# MINIOLED.net
KiCad netlist of a schematic drawn in Altium Designer
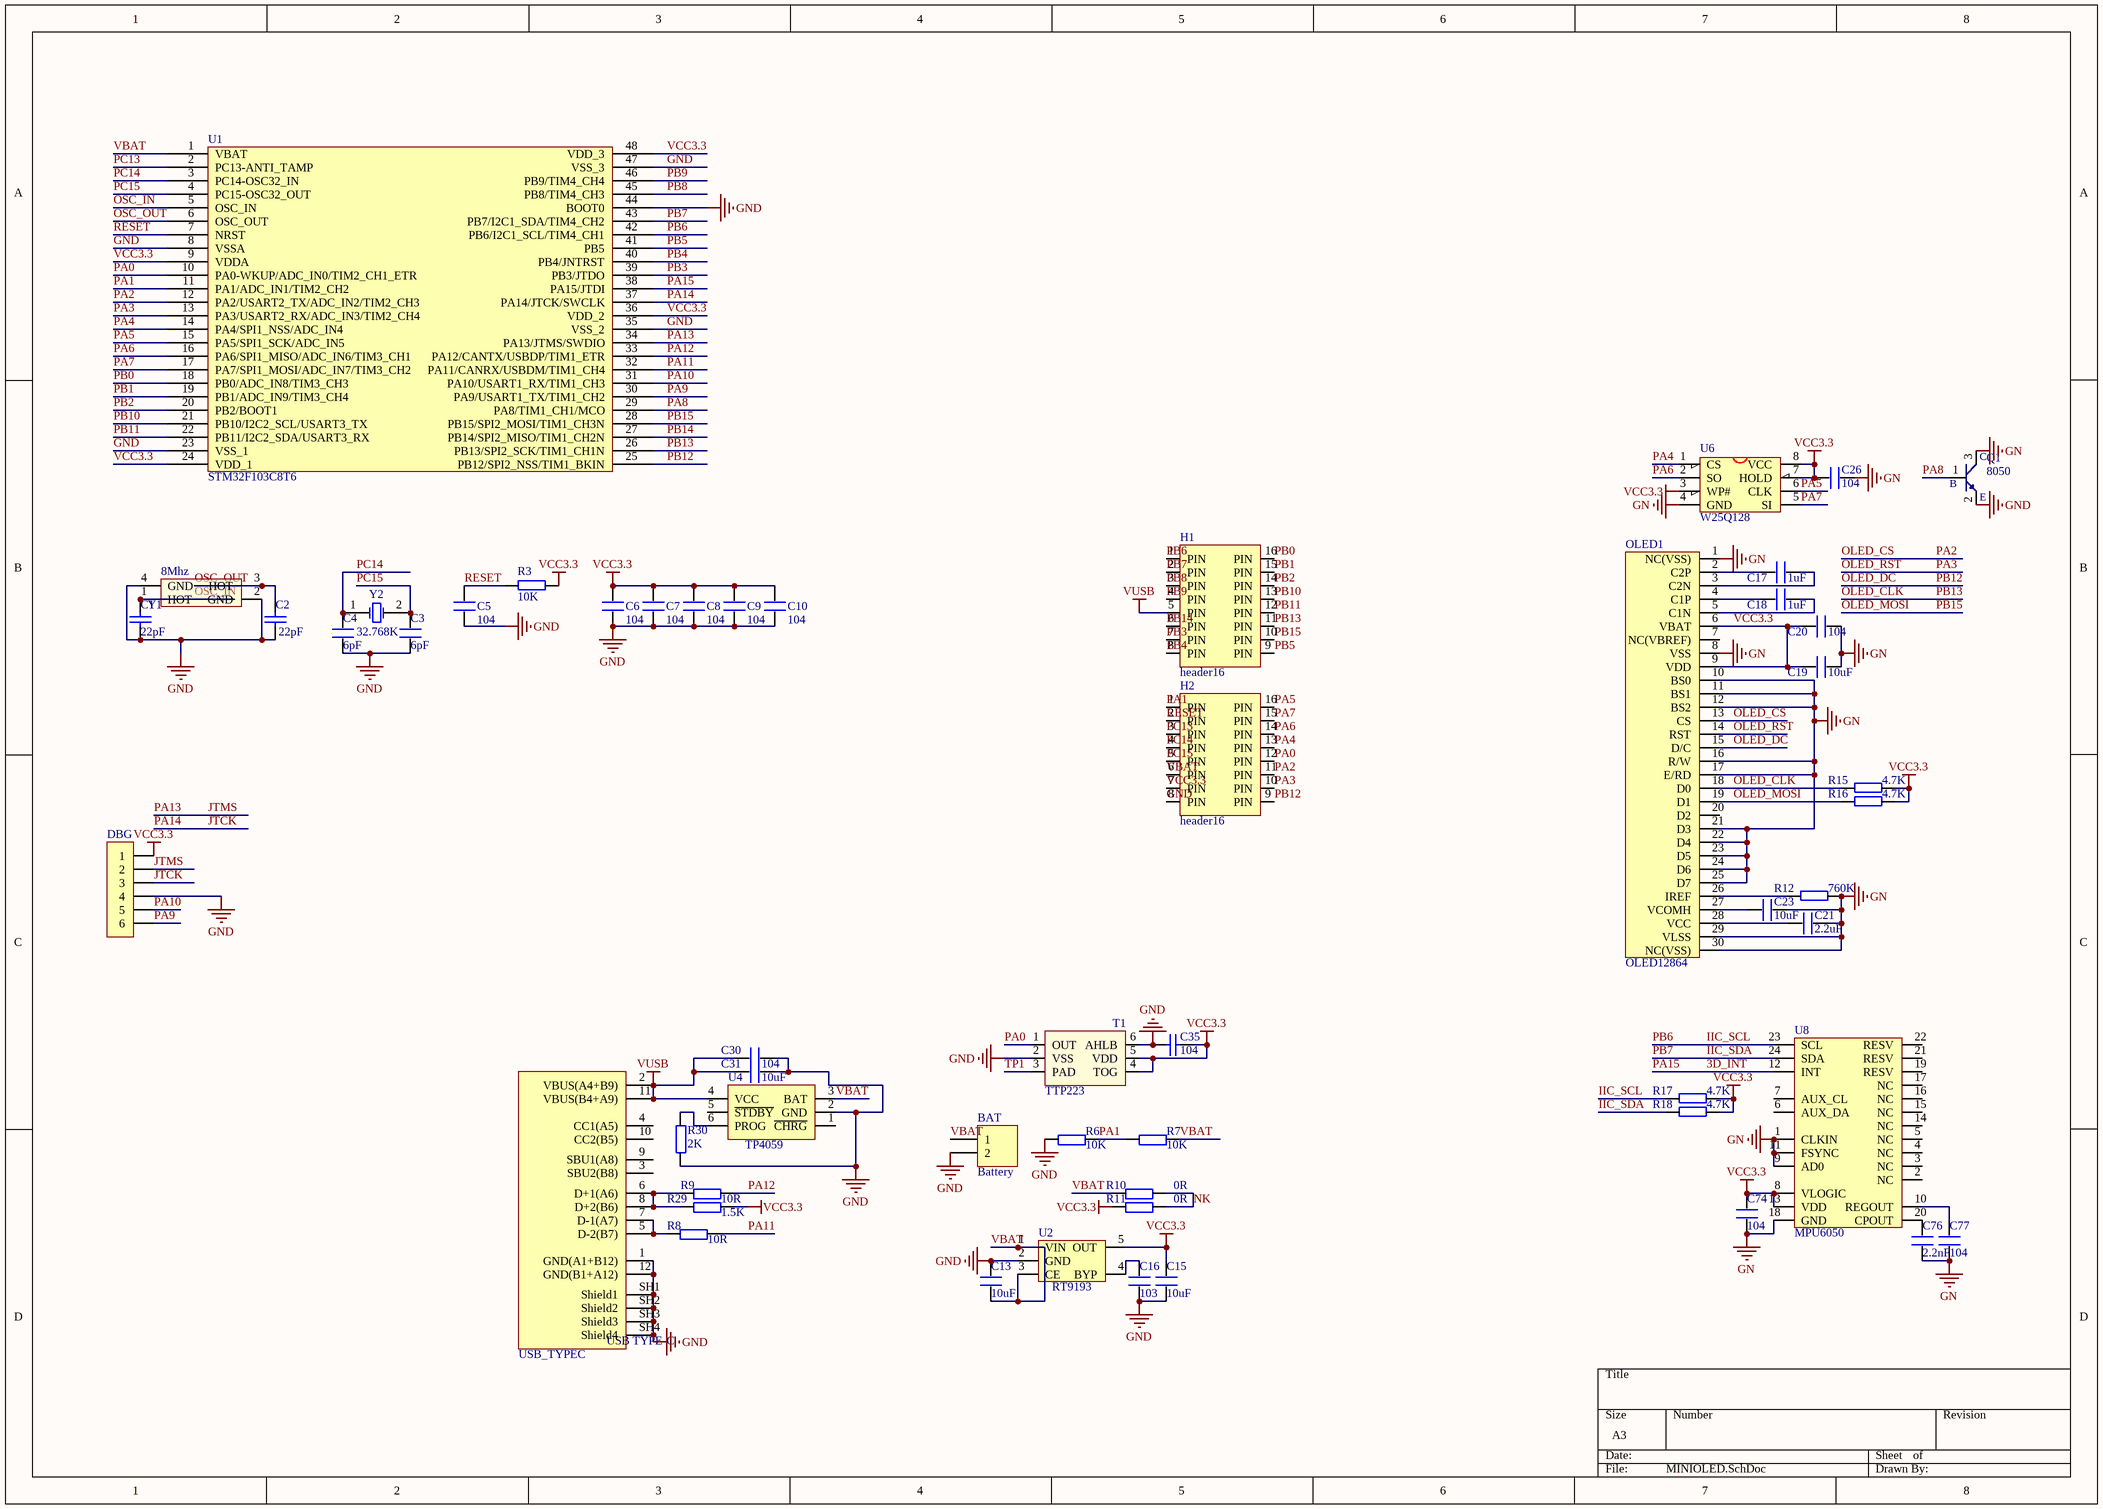
[diagram p0: MINIOLED.SchDoc]

(export (version "E")
  (design (tool "Eeschema 10.0.6"))
  (components
    (comp (ref "BAT")
      (value "Battery")
      (footprint "HDR2.54-LI-2P")
      (description "Header, 2-Pin")
      (fields (field (name "PUBLISHER") "Altium Limited"))
      (libsource (lib "MiniFly ") (part "Header 2"))
    )
    (comp (ref "C1") (value "22pF") (footprint "C 0603_L") (libsource (lib "L476") (part "CAP")))
    (comp (ref "C2") (value "22pF") (footprint "C 0603_L") (libsource (lib "L476") (part "CAP")))
    (comp (ref "C3")
      (value "6pF")
      (footprint "C 0603_L")
      (libsource (lib "WarShip V3 STM32103封装库") (part "C"))
    )
    (comp (ref "C4")
      (value "6pF")
      (footprint "C 0603_L")
      (libsource (lib "WarShip V3 STM32103封装库") (part "C"))
    )
    (comp (ref "C5")
      (value "104")
      (footprint "C 0603_L")
      (libsource (lib "WarShip V3 STM32103封装库") (part "C"))
    )
    (comp (ref "C6")
      (value "104")
      (footprint "C 0603_L")
      (libsource (lib "WarShip V3 STM32103封装库") (part "C"))
    )
    (comp (ref "C7")
      (value "104")
      (footprint "C 0603_L")
      (libsource (lib "WarShip V3 STM32103封装库") (part "C"))
    )
    (comp (ref "C8")
      (value "104")
      (footprint "C 0603_L")
      (libsource (lib "WarShip V3 STM32103封装库") (part "C"))
    )
    (comp (ref "C9")
      (value "104")
      (footprint "C 0603_L")
      (libsource (lib "WarShip V3 STM32103封装库") (part "C"))
    )
    (comp (ref "C10")
      (value "104")
      (footprint "C 0603_L")
      (libsource (lib "WarShip V3 STM32103封装库") (part "C"))
    )
    (comp (ref "C13")
      (value "10uF")
      (footprint "C 0603_L")
      (libsource (lib "WarShip V3 STM32103封装库") (part "C"))
    )
    (comp (ref "C15")
      (value "10uF")
      (footprint "C 0603_L")
      (libsource (lib "WarShip V3 STM32103封装库") (part "C"))
    )
    (comp (ref "C16")
      (value "103")
      (footprint "C 0603_L")
      (libsource (lib "WarShip V3 STM32103封装库") (part "C"))
    )
    (comp (ref "C17")
      (value "1uF")
      (footprint "C 0603_L")
      (libsource (lib "WarShip V3 STM32103封装库") (part "C"))
    )
    (comp (ref "C18")
      (value "1uF")
      (footprint "C 0603_L")
      (libsource (lib "WarShip V3 STM32103封装库") (part "C"))
    )
    (comp (ref "C19")
      (value "10uF")
      (footprint "C 0603_L")
      (libsource (lib "WarShip V3 STM32103封装库") (part "C"))
    )
    (comp (ref "C20")
      (value "104")
      (footprint "C 0603_L")
      (libsource (lib "WarShip V3 STM32103封装库") (part "C"))
    )
    (comp (ref "C21")
      (value "2.2uF")
      (footprint "C 0603_L")
      (libsource (lib "WarShip V3 STM32103封装库") (part "C"))
    )
    (comp (ref "C23")
      (value "10uF")
      (footprint "C 0603_L")
      (libsource (lib "WarShip V3 STM32103封装库") (part "C"))
    )
    (comp (ref "C26")
      (value "104")
      (footprint "C 0603_L")
      (libsource (lib "WarShip V3 STM32103封装库") (part "C"))
    )
    (comp (ref "C30")
      (value "104")
      (footprint "C 0603_L")
      (libsource (lib "WarShip V3 STM32103封装库") (part "C"))
    )
    (comp (ref "C31")
      (value "10uF")
      (footprint "C 0603_L")
      (libsource (lib "WarShip V3 STM32103封装库") (part "C"))
    )
    (comp (ref "C35")
      (value "104")
      (footprint "C 0603_L")
      (libsource (lib "Pandora_STM32L4_Board_V2.4") (part "C-0603-SMD"))
    )
    (comp (ref "C74") (value "104") (footprint "C 0603_L") (libsource (lib "MYCOMLIB") (part "C")))
    (comp (ref "C76") (value "2.2nF") (footprint "C 0603_L") (libsource (lib "MYCOMLIB") (part "C")))
    (comp (ref "C77") (value "104") (footprint "C 0603_L") (libsource (lib "MYCOMLIB") (part "C")))
    (comp (ref "DBG")
      (value "GPS&COMPASS")
      (footprint "SH1.0_6P")
      (description "6P接插件")
      (fields (field (name "版权归属") "源创客"))
      (libsource (lib "ATKF405 V1.1") (part "Header 6"))
    )
    (comp (ref "H1")
      (value "header16")
      (footprint "F_16PIN")
      (description "表贴母座16P")
      (libsource (lib "LovelessingSch") (part "Header2X8"))
    )
    (comp (ref "H2")
      (value "header16")
      (footprint "F_16PIN")
      (description "表贴母座16P")
      (libsource (lib "LovelessingSch") (part "Header2X8"))
    )
    (comp (ref "OLED1")
      (value "OLED12864")
      (footprint "OLED1.3")
      (libsource (lib "OLED模块封装库") (part "OLED12864"))
    )
    (comp (ref "Q1")
      (value "8050")
      (footprint "SOT23-3L")
      (libsource (lib "LovelessingSch") (part "8050NPN"))
    )
    (comp (ref "R3")
      (value "10K")
      (footprint "R 0603_L")
      (libsource (lib "WarShip V3 STM32103封装库") (part "R"))
    )
    (comp (ref "R6")
      (value "10K")
      (footprint "R 0603_L")
      (libsource (lib "WarShip V3 STM32103封装库") (part "R"))
    )
    (comp (ref "R7")
      (value "10K")
      (footprint "R 0603_L")
      (libsource (lib "WarShip V3 STM32103封装库") (part "R"))
    )
    (comp (ref "R8")
      (value "10R")
      (footprint "R 0603_L")
      (libsource (lib "WarShip V3 STM32103封装库") (part "R"))
    )
    (comp (ref "R9")
      (value "10R")
      (footprint "R 0603_L")
      (libsource (lib "WarShip V3 STM32103封装库") (part "R"))
    )
    (comp (ref "R10")
      (value "0R")
      (footprint "R 0603_L")
      (libsource (lib "WarShip V3 STM32103封装库") (part "R"))
    )
    (comp (ref "R11")
      (value "0R")
      (footprint "R 0603_L")
      (libsource (lib "WarShip V3 STM32103封装库") (part "R"))
    )
    (comp (ref "R12")
      (value "760K")
      (footprint "R 0603_L")
      (libsource (lib "WarShip V3 STM32103封装库") (part "R"))
    )
    (comp (ref "R15")
      (value "4.7K")
      (footprint "R 0603_L")
      (libsource (lib "WarShip V3 STM32103封装库") (part "R"))
    )
    (comp (ref "R16")
      (value "4.7K")
      (footprint "R 0603_L")
      (libsource (lib "WarShip V3 STM32103封装库") (part "R"))
    )
    (comp (ref "R17")
      (value "4.7K")
      (footprint "R 0603_L")
      (libsource (lib "WarShip V3 STM32103封装库") (part "R"))
    )
    (comp (ref "R18")
      (value "4.7K")
      (footprint "R 0603_L")
      (libsource (lib "WarShip V3 STM32103封装库") (part "R"))
    )
    (comp (ref "R29")
      (value "1.5K")
      (footprint "R 0603_L")
      (libsource (lib "WarShip V3 STM32103封装库") (part "R"))
    )
    (comp (ref "R30")
      (value "2K")
      (footprint "R 0603_L")
      (libsource (lib "WarShip V3 STM32103封装库") (part "R"))
    )
    (comp (ref "T1")
      (value "TTP223")
      (footprint "SOT23-6L")
      (libsource (lib "nrf52832model") (part "TTP223"))
    )
    (comp (ref "U1")
      (value "STM32F103C8T6")
      (footprint "LQFP48 7X7_L")
      (libsource (lib "Pandora_STM32L4_Board_V2.4") (part "U-STM32F103C8T6"))
    )
    (comp (ref "U2")
      (value "RT9193")
      (footprint "SOT23-5L")
      (description "3.3V 500mA LDO")
      (libsource (lib "STM32H743核心板封装库") (part "CAT6219-330TD"))
    )
    (comp (ref "U4")
      (value "TP4059")
      (footprint "SOT23-6L")
      (libsource (lib "ATK-2014-09-12") (part "TP4059"))
    )
    (comp (ref "U6")
      (value "W25Q128")
      (footprint "SOP8W_L")
      (description "W25X16;SST25VF016;MX25L1605")
      (libsource (lib "WarShip V3 STM32103封装库") (part "W25X16"))
    )
    (comp (ref "U8")
      (value "MPU6050")
      (footprint "QFN24 4x4_N")
      (description "9轴运动处理传感器")
      (libsource (lib "ALIENTEK_COMPONENT") (part "MPU6050"))
    )
    (comp (ref "USB_TYPEC")
      (value "USB TypeC")
      (footprint "USB Type-C")
      (description "12P TypeC 母座")
      (libsource (lib "ESP32_Weather") (part "USB Type-C"))
    )
    (comp (ref "Y1")
      (value "8Mhz")
      (footprint "OSC32254Pmini")
      (description "3225贴片无源晶振")
      (libsource (lib "ALIENTEK_COMPONENT") (part "XTAL_3225"))
    )
    (comp (ref "Y2")
      (value "32.768K")
      (footprint "OSC 3215-2P")
      (description "Crystal Oscillator")
      (fields (field (name "PUBLISHER") "Altium Limited"))
      (libsource (lib "WarShip V3 STM32103封装库") (part "XTAL"))
    )
  )
  (nets
    (net (code "1") (name "/3D_INT") (class "Default")
      (node (ref "U1") (pin "38") (pinfunction "PA15/JTDI_38") (pintype "passive"))
      (node (ref "U8") (pin "12") (pinfunction "INT_12") (pintype "passive"))
    )
    (net (code "2") (name "/IIC_SCL") (class "Default")
      (node (ref "H1") (pin "1") (pinfunction "PIN_1") (pintype "passive"))
      (node (ref "R17") (pin "2") (pintype "passive"))
      (node (ref "U1") (pin "42") (pinfunction "PB6/I2C1_SCL/TIM4_CH1_42") (pintype "passive"))
      (node (ref "U8") (pin "23") (pinfunction "SCL_23") (pintype "passive"))
    )
    (net (code "3") (name "/IIC_SDA") (class "Default")
      (node (ref "H1") (pin "2") (pinfunction "PIN_2") (pintype "passive"))
      (node (ref "R18") (pin "2") (pintype "passive"))
      (node (ref "U1") (pin "43") (pinfunction "PB7/I2C1_SDA/TIM4_CH2_43") (pintype "passive"))
      (node (ref "U8") (pin "24") (pinfunction "SDA_24") (pintype "passive"))
    )
    (net (code "4") (name "/JTCK") (class "Default")
      (node (ref "DBG") (pin "3") (pinfunction "3_3") (pintype "passive"))
      (node (ref "U1") (pin "37") (pinfunction "PA14/JTCK/SWCLK_37") (pintype "passive"))
    )
    (net (code "5") (name "/JTMS") (class "Default")
      (node (ref "DBG") (pin "2") (pinfunction "2_2") (pintype "passive"))
      (node (ref "U1") (pin "34") (pinfunction "PA13/JTMS/SWDIO_34") (pintype "passive"))
    )
    (net (code "6") (name "/NK") (class "Default")
      (node (ref "R10") (pin "2") (pintype "passive"))
      (node (ref "R11") (pin "2") (pintype "passive"))
    )
    (net (code "7") (name "/OLED_CLK") (class "Default")
      (node (ref "H1") (pin "11") (pinfunction "PIN_11") (pintype "passive"))
      (node (ref "OLED1") (pin "18") (pinfunction "D0_18") (pintype "passive"))
      (node (ref "R15") (pin "2") (pintype "passive"))
      (node (ref "U1") (pin "26") (pinfunction "PB13/SPI2_SCK/TIM1_CH1N_26") (pintype "passive"))
    )
    (net (code "8") (name "/OLED_CS") (class "Default")
      (node (ref "H2") (pin "11") (pinfunction "PIN_11") (pintype "passive"))
      (node (ref "OLED1") (pin "13") (pinfunction "CS_13") (pintype "passive"))
      (node (ref "U1") (pin "12") (pinfunction "PA2/USART2_TX/ADC_IN2/TIM2_CH3_12") (pintype "passive"))
    )
    (net (code "9") (name "/OLED_DC") (class "Default")
      (node (ref "H2") (pin "9") (pinfunction "PIN_9") (pintype "passive"))
      (node (ref "OLED1") (pin "15") (pinfunction "D/C_15") (pintype "passive"))
      (node (ref "U1") (pin "25") (pinfunction "PB12/SPI2_NSS/TIM1_BKIN_25") (pintype "passive"))
    )
    (net (code "10") (name "/OLED_MOSI") (class "Default")
      (node (ref "H1") (pin "10") (pinfunction "PIN_10") (pintype "passive"))
      (node (ref "OLED1") (pin "19") (pinfunction "D1_19") (pintype "passive"))
      (node (ref "R16") (pin "2") (pintype "passive"))
      (node (ref "U1") (pin "28") (pinfunction "PB15/SPI2_MOSI/TIM1_CH3N_28") (pintype "passive"))
    )
    (net (code "11") (name "/OLED_RST") (class "Default")
      (node (ref "H2") (pin "10") (pinfunction "PIN_10") (pintype "passive"))
      (node (ref "OLED1") (pin "14") (pinfunction "RST_14") (pintype "passive"))
      (node (ref "U1") (pin "13") (pinfunction "PA3/USART2_RX/ADC_IN3/TIM2_CH4_13") (pintype "passive"))
    )
    (net (code "12") (name "/OSC_IN") (class "Default")
      (node (ref "C1") (pin "2") (pinfunction "2_2") (pintype "passive"))
      (node (ref "U1") (pin "5") (pinfunction "OSC_IN_5") (pintype "passive"))
      (node (ref "Y1") (pin "1") (pinfunction "HOT_1") (pintype "passive"))
    )
    (net (code "13") (name "/OSC_OUT") (class "Default")
      (node (ref "C2") (pin "2") (pinfunction "2_2") (pintype "passive"))
      (node (ref "U1") (pin "6") (pinfunction "OSC_OUT_6") (pintype "passive"))
      (node (ref "Y1") (pin "3") (pinfunction "HOT_3") (pintype "passive"))
    )
    (net (code "14") (name "/PA0") (class "Default")
      (node (ref "H2") (pin "12") (pinfunction "PIN_12") (pintype "passive"))
      (node (ref "T1") (pin "1") (pinfunction "OUT_1") (pintype "passive"))
      (node (ref "U1") (pin "10") (pinfunction "PA0-WKUP/ADC_IN0/TIM2_CH1_ETR_10") (pintype "passive"))
    )
    (net (code "15") (name "/PA1") (class "Default")
      (node (ref "H2") (pin "1") (pinfunction "PIN_1") (pintype "passive"))
      (node (ref "R6") (pin "2") (pintype "passive"))
      (node (ref "R7") (pin "1") (pintype "passive"))
      (node (ref "U1") (pin "11") (pinfunction "PA1/ADC_IN1/TIM2_CH2_11") (pintype "passive"))
    )
    (net (code "16") (name "/PA4") (class "Default")
      (node (ref "H2") (pin "13") (pinfunction "PIN_13") (pintype "passive"))
      (node (ref "U1") (pin "14") (pinfunction "PA4/SPI1_NSS/ADC_IN4_14") (pintype "passive"))
      (node (ref "U6") (pin "1") (pinfunction "CS_1") (pintype "passive"))
    )
    (net (code "17") (name "/PA5") (class "Default")
      (node (ref "H2") (pin "16") (pinfunction "PIN_16") (pintype "passive"))
      (node (ref "U1") (pin "15") (pinfunction "PA5/SPI1_SCK/ADC_IN5_15") (pintype "passive"))
      (node (ref "U6") (pin "6") (pinfunction "CLK_6") (pintype "passive"))
    )
    (net (code "18") (name "/PA6") (class "Default")
      (node (ref "H2") (pin "14") (pinfunction "PIN_14") (pintype "passive"))
      (node (ref "U1") (pin "16") (pinfunction "PA6/SPI1_MISO/ADC_IN6/TIM3_CH1_16") (pintype "passive"))
      (node (ref "U6") (pin "2") (pinfunction "SO_2") (pintype "passive"))
    )
    (net (code "19") (name "/PA7") (class "Default")
      (node (ref "H2") (pin "15") (pinfunction "PIN_15") (pintype "passive"))
      (node (ref "U1") (pin "17") (pinfunction "PA7/SPI1_MOSI/ADC_IN7/TIM3_CH2_17") (pintype "passive"))
      (node (ref "U6") (pin "5") (pinfunction "SI_5") (pintype "passive"))
    )
    (net (code "20") (name "/PA8") (class "Default")
      (node (ref "Q1") (pin "1") (pinfunction "B_1") (pintype "passive"))
      (node (ref "U1") (pin "29") (pinfunction "PA8/TIM1_CH1/MCO_29") (pintype "passive"))
    )
    (net (code "21") (name "/PA9") (class "Default")
      (node (ref "DBG") (pin "6") (pinfunction "6_6") (pintype "passive"))
      (node (ref "U1") (pin "30") (pinfunction "PA9/USART1_TX/TIM1_CH2_30") (pintype "passive"))
    )
    (net (code "22") (name "/PA10") (class "Default")
      (node (ref "DBG") (pin "5") (pinfunction "5_5") (pintype "passive"))
      (node (ref "U1") (pin "31") (pinfunction "PA10/USART1_RX/TIM1_CH3_31") (pintype "passive"))
    )
    (net (code "23") (name "/PA11") (class "Default")
      (node (ref "R8") (pin "2") (pintype "passive"))
      (node (ref "U1") (pin "32") (pinfunction "PA11/CANRX/USBDM/TIM1_CH4_32") (pintype "passive"))
    )
    (net (code "24") (name "/PA12") (class "Default")
      (node (ref "R9") (pin "2") (pintype "passive"))
      (node (ref "U1") (pin "33") (pinfunction "PA12/CANTX/USBDP/TIM1_ETR_33") (pintype "passive"))
    )
    (net (code "25") (name "/PB0") (class "Default")
      (node (ref "H1") (pin "16") (pinfunction "PIN_16") (pintype "passive"))
      (node (ref "U1") (pin "18") (pinfunction "PB0/ADC_IN8/TIM3_CH3_18") (pintype "passive"))
    )
    (net (code "26") (name "/PB1") (class "Default")
      (node (ref "H1") (pin "15") (pinfunction "PIN_15") (pintype "passive"))
      (node (ref "U1") (pin "19") (pinfunction "PB1/ADC_IN9/TIM3_CH4_19") (pintype "passive"))
    )
    (net (code "27") (name "/PB2") (class "Default")
      (node (ref "H1") (pin "14") (pinfunction "PIN_14") (pintype "passive"))
      (node (ref "U1") (pin "20") (pinfunction "PB2/BOOT1_20") (pintype "passive"))
    )
    (net (code "28") (name "/PB3") (class "Default")
      (node (ref "H1") (pin "7") (pinfunction "PIN_7") (pintype "passive"))
      (node (ref "U1") (pin "39") (pinfunction "PB3/JTDO_39") (pintype "passive"))
    )
    (net (code "29") (name "/PB4") (class "Default")
      (node (ref "H1") (pin "8") (pinfunction "PIN_8") (pintype "passive"))
      (node (ref "U1") (pin "40") (pinfunction "PB4/JNTRST_40") (pintype "passive"))
    )
    (net (code "30") (name "/PB5") (class "Default")
      (node (ref "H1") (pin "9") (pinfunction "PIN_9") (pintype "passive"))
      (node (ref "U1") (pin "41") (pinfunction "PB5_41") (pintype "passive"))
    )
    (net (code "31") (name "/PB8") (class "Default")
      (node (ref "H1") (pin "3") (pinfunction "PIN_3") (pintype "passive"))
      (node (ref "U1") (pin "45") (pinfunction "PB8/TIM4_CH3_45") (pintype "passive"))
    )
    (net (code "32") (name "/PB9") (class "Default")
      (node (ref "H1") (pin "4") (pinfunction "PIN_4") (pintype "passive"))
      (node (ref "U1") (pin "46") (pinfunction "PB9/TIM4_CH4_46") (pintype "passive"))
    )
    (net (code "33") (name "/PB10") (class "Default")
      (node (ref "H1") (pin "13") (pinfunction "PIN_13") (pintype "passive"))
      (node (ref "U1") (pin "21") (pinfunction "PB10/I2C2_SCL/USART3_TX_21") (pintype "passive"))
    )
    (net (code "34") (name "/PB11") (class "Default")
      (node (ref "H1") (pin "12") (pinfunction "PIN_12") (pintype "passive"))
      (node (ref "U1") (pin "22") (pinfunction "PB11/I2C2_SDA/USART3_RX_22") (pintype "passive"))
    )
    (net (code "35") (name "/PB14") (class "Default")
      (node (ref "H1") (pin "6") (pinfunction "PIN_6") (pintype "passive"))
      (node (ref "U1") (pin "27") (pinfunction "PB14/SPI2_MISO/TIM1_CH2N_27") (pintype "passive"))
    )
    (net (code "36") (name "/PC13") (class "Default")
      (node (ref "H2") (pin "3") (pinfunction "PIN_3") (pintype "passive"))
      (node (ref "U1") (pin "2") (pinfunction "PC13-ANTI_TAMP_2") (pintype "passive"))
    )
    (net (code "37") (name "/PC14") (class "Default")
      (node (ref "C4") (pin "2") (pintype "passive"))
      (node (ref "H2") (pin "4") (pinfunction "PIN_4") (pintype "passive"))
      (node (ref "U1") (pin "3") (pinfunction "PC14-OSC32_IN_3") (pintype "passive"))
      (node (ref "Y2") (pin "1") (pinfunction "OSC1_1") (pintype "passive"))
    )
    (net (code "38") (name "/PC15") (class "Default")
      (node (ref "C3") (pin "2") (pintype "passive"))
      (node (ref "H2") (pin "5") (pinfunction "PIN_5") (pintype "passive"))
      (node (ref "U1") (pin "4") (pinfunction "PC15-OSC32_OUT_4") (pintype "passive"))
      (node (ref "Y2") (pin "2") (pinfunction "OSC2_2") (pintype "passive"))
    )
    (net (code "39") (name "/RESET") (class "Default")
      (node (ref "C5") (pin "2") (pintype "passive"))
      (node (ref "H2") (pin "2") (pinfunction "PIN_2") (pintype "passive"))
      (node (ref "R3") (pin "2") (pintype "passive"))
      (node (ref "U1") (pin "7") (pinfunction "NRST_7") (pintype "passive"))
    )
    (net (code "40") (name "/TP1") (class "Default")
      (node (ref "T1") (pin "3") (pinfunction "PAD_3") (pintype "passive"))
    )
    (net (code "41") (name "/VBAT") (class "Default")
      (node (ref "BAT") (pin "1") (pinfunction "1_1") (pintype "passive"))
      (node (ref "C13") (pin "1") (pintype "passive"))
      (node (ref "H2") (pin "6") (pinfunction "PIN_6") (pintype "passive"))
      (node (ref "R10") (pin "1") (pintype "passive"))
      (node (ref "R7") (pin "2") (pintype "passive"))
      (node (ref "U1") (pin "1") (pinfunction "VBAT_1") (pintype "passive"))
      (node (ref "U2") (pin "1") (pinfunction "VIN_1") (pintype "passive"))
      (node (ref "U2") (pin "3") (pinfunction "CE_3") (pintype "passive"))
      (node (ref "U4") (pin "3") (pinfunction "BAT_3") (pintype "passive"))
    )
    (net (code "42") (name "GN") (class "Default")
      (node (ref "C19") (pin "1") (pintype "passive"))
      (node (ref "C20") (pin "1") (pintype "passive"))
      (node (ref "C21") (pin "1") (pintype "passive"))
      (node (ref "C23") (pin "1") (pintype "passive"))
      (node (ref "C26") (pin "2") (pintype "passive"))
      (node (ref "C74") (pin "1") (pintype "passive"))
      (node (ref "C76") (pin "1") (pintype "passive"))
      (node (ref "C77") (pin "2") (pintype "passive"))
      (node (ref "OLED1") (pin "1") (pinfunction "NC(VSS)_1") (pintype "passive"))
      (node (ref "OLED1") (pin "10") (pinfunction "BS0_10") (pintype "passive"))
      (node (ref "OLED1") (pin "11") (pinfunction "BS1_11") (pintype "passive"))
      (node (ref "OLED1") (pin "12") (pinfunction "BS2_12") (pintype "passive"))
      (node (ref "OLED1") (pin "16") (pinfunction "R/W_16") (pintype "passive"))
      (node (ref "OLED1") (pin "17") (pinfunction "E/RD_17") (pintype "passive"))
      (node (ref "OLED1") (pin "21") (pinfunction "D3_21") (pintype "passive"))
      (node (ref "OLED1") (pin "22") (pinfunction "D4_22") (pintype "passive"))
      (node (ref "OLED1") (pin "23") (pinfunction "D5_23") (pintype "passive"))
      (node (ref "OLED1") (pin "24") (pinfunction "D6_24") (pintype "passive"))
      (node (ref "OLED1") (pin "25") (pinfunction "D7_25") (pintype "passive"))
      (node (ref "OLED1") (pin "29") (pinfunction "VLSS_29") (pintype "passive"))
      (node (ref "OLED1") (pin "30") (pinfunction "NC(VSS)_30") (pintype "passive"))
      (node (ref "OLED1") (pin "8") (pinfunction "VSS_8") (pintype "passive"))
      (node (ref "Q1") (pin "3") (pinfunction "C_3") (pintype "passive"))
      (node (ref "R12") (pin "1") (pintype "passive"))
      (node (ref "U6") (pin "4") (pinfunction "GND_4") (pintype "passive"))
      (node (ref "U8") (pin "1") (pinfunction "CLKIN_1") (pintype "passive"))
      (node (ref "U8") (pin "11") (pinfunction "FSYNC_11") (pintype "passive"))
      (node (ref "U8") (pin "18") (pinfunction "GND_18") (pintype "passive"))
      (node (ref "U8") (pin "9") (pinfunction "AD0_9") (pintype "passive"))
    )
    (net (code "43") (name "GND") (class "Default")
      (node (ref "BAT") (pin "2") (pinfunction "2_2") (pintype "passive"))
      (node (ref "C1") (pin "1") (pinfunction "1_1") (pintype "passive"))
      (node (ref "C10") (pin "1") (pintype "passive"))
      (node (ref "C13") (pin "2") (pintype "passive"))
      (node (ref "C15") (pin "1") (pintype "passive"))
      (node (ref "C16") (pin "1") (pintype "passive"))
      (node (ref "C2") (pin "1") (pinfunction "1_1") (pintype "passive"))
      (node (ref "C3") (pin "1") (pintype "passive"))
      (node (ref "C30") (pin "1") (pintype "passive"))
      (node (ref "C31") (pin "1") (pintype "passive"))
      (node (ref "C35") (pin "2") (pinfunction "2_2") (pintype "passive"))
      (node (ref "C4") (pin "1") (pintype "passive"))
      (node (ref "C5") (pin "1") (pintype "passive"))
      (node (ref "C6") (pin "1") (pintype "passive"))
      (node (ref "C7") (pin "1") (pintype "passive"))
      (node (ref "C8") (pin "1") (pintype "passive"))
      (node (ref "C9") (pin "1") (pintype "passive"))
      (node (ref "DBG") (pin "4") (pinfunction "4_4") (pintype "passive"))
      (node (ref "H2") (pin "8") (pinfunction "PIN_8") (pintype "passive"))
      (node (ref "Q1") (pin "2") (pinfunction "E_2") (pintype "passive"))
      (node (ref "R30") (pin "1") (pintype "passive"))
      (node (ref "R6") (pin "1") (pintype "passive"))
      (node (ref "T1") (pin "2") (pinfunction "VSS_2") (pintype "passive"))
      (node (ref "T1") (pin "6") (pinfunction "AHLB_6") (pintype "passive"))
      (node (ref "U1") (pin "23") (pinfunction "VSS_1_23") (pintype "passive"))
      (node (ref "U1") (pin "35") (pinfunction "VSS_2_35") (pintype "passive"))
      (node (ref "U1") (pin "44") (pinfunction "BOOT0_44") (pintype "passive"))
      (node (ref "U1") (pin "47") (pinfunction "VSS_3_47") (pintype "passive"))
      (node (ref "U1") (pin "8") (pinfunction "VSSA_8") (pintype "passive"))
      (node (ref "U2") (pin "2") (pinfunction "GND_2") (pintype "passive"))
      (node (ref "U4") (pin "2") (pinfunction "GND_2") (pintype "passive"))
      (node (ref "USB_TYPEC") (pin "1") (pinfunction "GND(A1+B12)_1") (pintype "passive"))
      (node (ref "USB_TYPEC") (pin "12") (pinfunction "GND(B1+A12)_12") (pintype "passive"))
      (node (ref "USB_TYPEC") (pin "SH1") (pinfunction "Shield1_SH1") (pintype "passive"))
      (node (ref "USB_TYPEC") (pin "SH2") (pinfunction "Shield2_SH2") (pintype "passive"))
      (node (ref "USB_TYPEC") (pin "SH3") (pinfunction "Shield3_SH3") (pintype "passive"))
      (node (ref "USB_TYPEC") (pin "SH4") (pinfunction "Shield4_SH4") (pintype "passive"))
      (node (ref "Y1") (pin "2") (pinfunction "GND_2") (pintype "passive"))
      (node (ref "Y1") (pin "4") (pinfunction "GND_4") (pintype "passive"))
    )
    (net (code "44") (name "Net-(OLED1-C1N)") (class "Default")
      (node (ref "C18") (pin "1") (pintype "passive"))
      (node (ref "OLED1") (pin "5") (pinfunction "C1N_5") (pintype "passive"))
    )
    (net (code "45") (name "Net-(OLED1-C1P)") (class "Default")
      (node (ref "C18") (pin "2") (pintype "passive"))
      (node (ref "OLED1") (pin "4") (pinfunction "C1P_4") (pintype "passive"))
    )
    (net (code "46") (name "Net-(OLED1-C2N)") (class "Default")
      (node (ref "C17") (pin "1") (pintype "passive"))
      (node (ref "OLED1") (pin "3") (pinfunction "C2N_3") (pintype "passive"))
    )
    (net (code "47") (name "Net-(OLED1-C2P)") (class "Default")
      (node (ref "C17") (pin "2") (pintype "passive"))
      (node (ref "OLED1") (pin "2") (pinfunction "C2P_2") (pintype "passive"))
    )
    (net (code "48") (name "Net-(OLED1-IREF)") (class "Default")
      (node (ref "OLED1") (pin "26") (pinfunction "IREF_26") (pintype "passive"))
      (node (ref "R12") (pin "2") (pintype "passive"))
    )
    (net (code "49") (name "Net-(OLED1-VCC)") (class "Default")
      (node (ref "C21") (pin "2") (pintype "passive"))
      (node (ref "OLED1") (pin "28") (pinfunction "VCC_28") (pintype "passive"))
    )
    (net (code "50") (name "Net-(OLED1-VCOMH)") (class "Default")
      (node (ref "C23") (pin "2") (pintype "passive"))
      (node (ref "OLED1") (pin "27") (pinfunction "VCOMH_27") (pintype "passive"))
    )
    (net (code "51") (name "Net-(U2-BYP)") (class "Default")
      (node (ref "C16") (pin "2") (pintype "passive"))
      (node (ref "U2") (pin "4") (pinfunction "BYP_4") (pintype "passive"))
    )
    (net (code "52") (name "Net-(U4-PROG)") (class "Default")
      (node (ref "R30") (pin "2") (pintype "passive"))
      (node (ref "U4") (pin "6") (pinfunction "PROG_6") (pintype "passive"))
    )
    (net (code "53") (name "Net-(U8-CPOUT)") (class "Default")
      (node (ref "C76") (pin "2") (pintype "passive"))
      (node (ref "U8") (pin "20") (pinfunction "CPOUT_20") (pintype "passive"))
    )
    (net (code "54") (name "Net-(U8-REGOUT)") (class "Default")
      (node (ref "C77") (pin "1") (pintype "passive"))
      (node (ref "U8") (pin "10") (pinfunction "REGOUT_10") (pintype "passive"))
    )
    (net (code "55") (name "Net-(USB_TYPEC-D+1(A6))") (class "Default")
      (node (ref "R29") (pin "1") (pintype "passive"))
      (node (ref "R9") (pin "1") (pintype "passive"))
      (node (ref "USB_TYPEC") (pin "6") (pinfunction "D+1(A6)_6") (pintype "passive"))
      (node (ref "USB_TYPEC") (pin "8") (pinfunction "D+2(B6)_8") (pintype "passive"))
    )
    (net (code "56") (name "Net-(USB_TYPEC-D-1(A7))") (class "Default")
      (node (ref "R8") (pin "1") (pintype "passive"))
      (node (ref "USB_TYPEC") (pin "5") (pinfunction "D-2(B7)_5") (pintype "passive"))
      (node (ref "USB_TYPEC") (pin "7") (pinfunction "D-1(A7)_7") (pintype "passive"))
    )
    (net (code "57") (name "VCC3.3") (class "Default")
      (node (ref "C10") (pin "2") (pintype "passive"))
      (node (ref "C15") (pin "2") (pintype "passive"))
      (node (ref "C19") (pin "2") (pintype "passive"))
      (node (ref "C20") (pin "2") (pintype "passive"))
      (node (ref "C26") (pin "1") (pintype "passive"))
      (node (ref "C35") (pin "1") (pinfunction "1_1") (pintype "passive"))
      (node (ref "C6") (pin "2") (pintype "passive"))
      (node (ref "C7") (pin "2") (pintype "passive"))
      (node (ref "C74") (pin "2") (pintype "passive"))
      (node (ref "C8") (pin "2") (pintype "passive"))
      (node (ref "C9") (pin "2") (pintype "passive"))
      (node (ref "DBG") (pin "1") (pinfunction "1_1") (pintype "passive"))
      (node (ref "H2") (pin "7") (pinfunction "PIN_7") (pintype "passive"))
      (node (ref "OLED1") (pin "6") (pinfunction "VBAT_6") (pintype "passive"))
      (node (ref "OLED1") (pin "9") (pinfunction "VDD_9") (pintype "passive"))
      (node (ref "R11") (pin "1") (pintype "passive"))
      (node (ref "R15") (pin "1") (pintype "passive"))
      (node (ref "R16") (pin "1") (pintype "passive"))
      (node (ref "R17") (pin "1") (pintype "passive"))
      (node (ref "R18") (pin "1") (pintype "passive"))
      (node (ref "R29") (pin "2") (pintype "passive"))
      (node (ref "R3") (pin "1") (pintype "passive"))
      (node (ref "T1") (pin "4") (pinfunction "TOG_4") (pintype "passive"))
      (node (ref "T1") (pin "5") (pinfunction "VDD_5") (pintype "passive"))
      (node (ref "U1") (pin "24") (pinfunction "VDD_1_24") (pintype "passive"))
      (node (ref "U1") (pin "36") (pinfunction "VDD_2_36") (pintype "passive"))
      (node (ref "U1") (pin "48") (pinfunction "VDD_3_48") (pintype "passive"))
      (node (ref "U1") (pin "9") (pinfunction "VDDA_9") (pintype "passive"))
      (node (ref "U2") (pin "5") (pinfunction "OUT_5") (pintype "passive"))
      (node (ref "U6") (pin "3") (pinfunction "WP#_3") (pintype "passive"))
      (node (ref "U6") (pin "7") (pinfunction "HOLD_7") (pintype "passive"))
      (node (ref "U6") (pin "8") (pinfunction "VCC_8") (pintype "passive"))
      (node (ref "U8") (pin "13") (pinfunction "VDD_13") (pintype "passive"))
      (node (ref "U8") (pin "8") (pinfunction "VLOGIC_8") (pintype "passive"))
    )
    (net (code "58") (name "VUSB") (class "Default")
      (node (ref "C30") (pin "2") (pintype "passive"))
      (node (ref "C31") (pin "2") (pintype "passive"))
      (node (ref "H1") (pin "5") (pinfunction "PIN_5") (pintype "passive"))
      (node (ref "U4") (pin "4") (pinfunction "VCC_4") (pintype "passive"))
      (node (ref "USB_TYPEC") (pin "11") (pinfunction "VBUS(B4+A9)_11") (pintype "passive"))
      (node (ref "USB_TYPEC") (pin "2") (pinfunction "VBUS(A4+B9)_2") (pintype "passive"))
    )
    (net (code "59") (name "unconnected-(OLED1-D2-Pad20)") (class "Default")
      (node (ref "OLED1") (pin "20") (pinfunction "D2_20") (pintype "passive"))
    )
    (net (code "60") (name "unconnected-(OLED1-NC(VBREF)-Pad7)") (class "Default")
      (node (ref "OLED1") (pin "7") (pinfunction "NC(VBREF)_7") (pintype "passive"))
    )
    (net (code "61") (name "unconnected-(U4-~{CHRG}-Pad1)") (class "Default")
      (node (ref "U4") (pin "1") (pinfunction "~{CHRG}_1") (pintype "passive"))
    )
    (net (code "62") (name "unconnected-(U4-~{STDBY}-Pad5)") (class "Default")
      (node (ref "U4") (pin "5") (pinfunction "~{STDBY}_5") (pintype "passive"))
    )
    (net (code "63") (name "unconnected-(U8-AUX_CL-Pad7)") (class "Default")
      (node (ref "U8") (pin "7") (pinfunction "AUX_CL_7") (pintype "passive"))
    )
    (net (code "64") (name "unconnected-(U8-AUX_DA-Pad6)") (class "Default")
      (node (ref "U8") (pin "6") (pinfunction "AUX_DA_6") (pintype "passive"))
    )
    (net (code "65") (name "unconnected-(U8-NC-Pad2)") (class "Default")
      (node (ref "U8") (pin "2") (pinfunction "NC_2") (pintype "passive"))
    )
    (net (code "66") (name "unconnected-(U8-NC-Pad3)") (class "Default")
      (node (ref "U8") (pin "3") (pinfunction "NC_3") (pintype "passive"))
    )
    (net (code "67") (name "unconnected-(U8-NC-Pad4)") (class "Default")
      (node (ref "U8") (pin "4") (pinfunction "NC_4") (pintype "passive"))
    )
    (net (code "68") (name "unconnected-(U8-NC-Pad5)") (class "Default")
      (node (ref "U8") (pin "5") (pinfunction "NC_5") (pintype "passive"))
    )
    (net (code "69") (name "unconnected-(U8-NC-Pad14)") (class "Default")
      (node (ref "U8") (pin "14") (pinfunction "NC_14") (pintype "passive"))
    )
    (net (code "70") (name "unconnected-(U8-NC-Pad15)") (class "Default")
      (node (ref "U8") (pin "15") (pinfunction "NC_15") (pintype "passive"))
    )
    (net (code "71") (name "unconnected-(U8-NC-Pad16)") (class "Default")
      (node (ref "U8") (pin "16") (pinfunction "NC_16") (pintype "passive"))
    )
    (net (code "72") (name "unconnected-(U8-NC-Pad17)") (class "Default")
      (node (ref "U8") (pin "17") (pinfunction "NC_17") (pintype "passive"))
    )
    (net (code "73") (name "unconnected-(U8-RESV-Pad19)") (class "Default")
      (node (ref "U8") (pin "19") (pinfunction "RESV_19") (pintype "passive"))
    )
    (net (code "74") (name "unconnected-(U8-RESV-Pad21)") (class "Default")
      (node (ref "U8") (pin "21") (pinfunction "RESV_21") (pintype "passive"))
    )
    (net (code "75") (name "unconnected-(U8-RESV-Pad22)") (class "Default")
      (node (ref "U8") (pin "22") (pinfunction "RESV_22") (pintype "passive"))
    )
    (net (code "76") (name "unconnected-(USB_TYPEC-CC1(A5)-Pad4)") (class "Default")
      (node (ref "USB_TYPEC") (pin "4") (pinfunction "CC1(A5)_4") (pintype "passive"))
    )
    (net (code "77") (name "unconnected-(USB_TYPEC-CC2(B5)-Pad10)") (class "Default")
      (node (ref "USB_TYPEC") (pin "10") (pinfunction "CC2(B5)_10") (pintype "passive"))
    )
    (net (code "78") (name "unconnected-(USB_TYPEC-SBU1(A8)-Pad9)") (class "Default")
      (node (ref "USB_TYPEC") (pin "9") (pinfunction "SBU1(A8)_9") (pintype "passive"))
    )
    (net (code "79") (name "unconnected-(USB_TYPEC-SBU2(B8)-Pad3)") (class "Default")
      (node (ref "USB_TYPEC") (pin "3") (pinfunction "SBU2(B8)_3") (pintype "passive"))
    )
  )
)
